# Schematic.net
KiCad netlist of a schematic drawn in Altium Designer
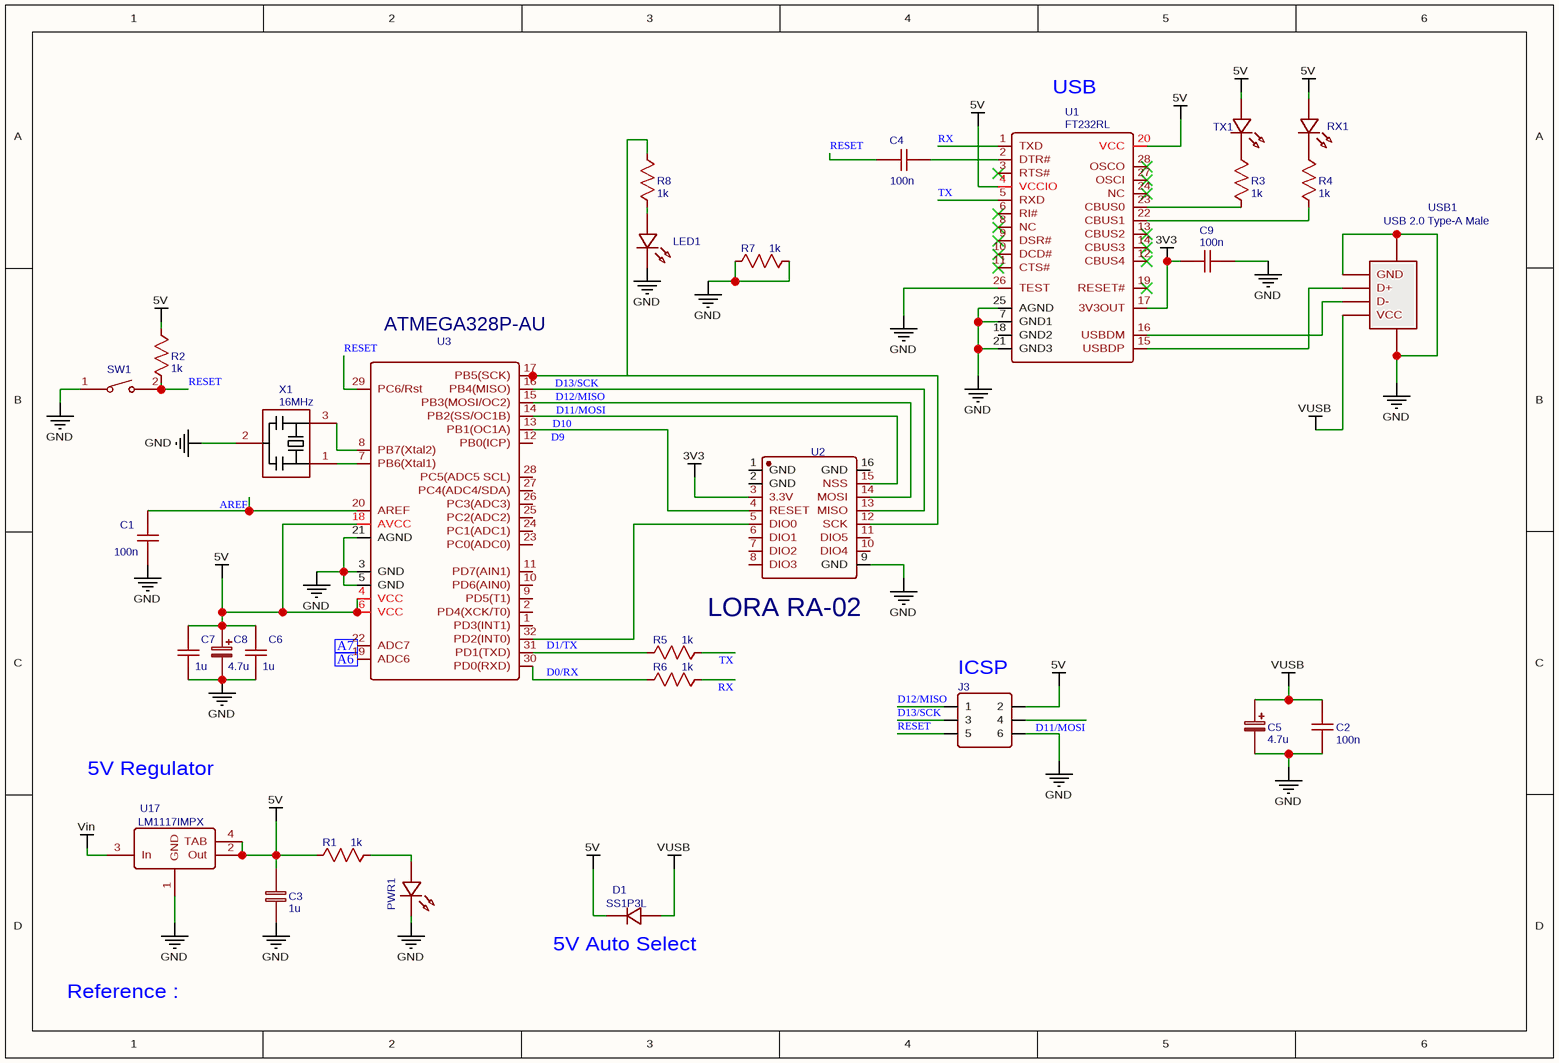
[diagram p0: Schematic.schdoc]

(export (version "E")
  (design (tool "Eeschema 10.0.6"))
  (components
    (comp (ref "C1")
      (value "100n")
      (fields (field (name "CONTRIBUTOR") "LCEDA_Lib"))
      (libsource (lib "altium-import") (part "root_3_100n_"))
    )
    (comp (ref "C2")
      (value "100n")
      (fields (field (name "CONTRIBUTOR") "LCEDA_Lib"))
      (libsource (lib "altium-import") (part "root_3_100n_"))
    )
    (comp (ref "C3")
      (value "1u")
      (fields (field (name "CONTRIBUTOR") "LCEDA_Lib"))
      (libsource (lib "altium-import") (part "root_1_1u_"))
    )
    (comp (ref "C4")
      (value "100n")
      (fields (field (name "CONTRIBUTOR") "LCEDA_Lib"))
      (libsource (lib "altium-import") (part "root_2_100n_"))
    )
    (comp (ref "C5")
      (value "4.7u")
      (fields (field (name "CONTRIBUTOR") "LCEDA_Lib"))
      (libsource (lib "altium-import") (part "root_3_4.7u_"))
    )
    (comp (ref "C6")
      (value "1u")
      (fields (field (name "CONTRIBUTOR") "LCEDA_Lib"))
      (libsource (lib "") (part "root_1_1u__1"))
    )
    (comp (ref "C7")
      (value "1u")
      (fields (field (name "CONTRIBUTOR") "LCEDA_Lib"))
      (libsource (lib "") (part "root_1_1u__1"))
    )
    (comp (ref "C8")
      (value "4.7u")
      (fields (field (name "CONTRIBUTOR") "LCEDA_Lib"))
      (libsource (lib "altium-import") (part "root_3_4.7u_"))
    )
    (comp (ref "C9")
      (value "100n")
      (fields (field (name "CONTRIBUTOR") "LCEDA_Lib"))
      (libsource (lib "altium-import") (part "root_0_100n_"))
    )
    (comp (ref "D1")
      (value "SS1P3L")
      (fields
        (field (name "MANUFACTURER") "Tak Cheong")
        (field (name "MANUFACTURER PART") "1N4148W")
        (field (name "CONTRIBUTOR") "LCEDA_Lib")
      )
      (libsource (lib "altium-import") (part "root_2_SS1P3L_"))
    )
    (comp (ref "J3")
      (value "HDR-M-2.54_2x3")
      (fields (field (name "CONTRIBUTOR") "LCEDA_Lib"))
      (libsource (lib "altium-import") (part "root_0_HDR-M-2.54_2x3_"))
    )
    (comp (ref "LED1")
      (value "LED-0603_B")
      (fields
        (field (name "MANUFACTURER") "EVERLIGHT(台湾亿光)")
        (field (name "MANUFACTURER PART") "19-217/BHC-ZL1M2RY/3T")
        (field (name "CONTRIBUTOR") "LCEDA_01")
      )
      (libsource (lib "altium-import") (part "root_3_LED-0603_B_"))
    )
    (comp (ref "PWR1")
      (value "LED-0603_G")
      (fields
        (field (name "MANUFACTURER") "EVERLIGHT(台湾亿光)")
        (field (name "MANUFACTURER PART") "19-217/GHC-YR1S2/3T")
        (field (name "CONTRIBUTOR") "LCEDA_Lib")
      )
      (libsource (lib "altium-import") (part "root_3_LED-0603_G_"))
    )
    (comp (ref "R1")
      (value "1k")
      (fields (field (name "CONTRIBUTOR") "LCEDA_Lib"))
      (libsource (lib "altium-import") (part "root_2_1k_"))
    )
    (comp (ref "R2")
      (value "1k")
      (fields (field (name "CONTRIBUTOR") "LCEDA_Lib"))
      (libsource (lib "altium-import") (part "root_1_1k_"))
    )
    (comp (ref "R3")
      (value "1k")
      (fields (field (name "CONTRIBUTOR") "LCEDA_Lib"))
      (libsource (lib "altium-import") (part "root_3_1k_"))
    )
    (comp (ref "R4")
      (value "1k")
      (fields (field (name "CONTRIBUTOR") "LCEDA_Lib"))
      (libsource (lib "altium-import") (part "root_3_1k_"))
    )
    (comp (ref "R5")
      (value "1k")
      (fields (field (name "CONTRIBUTOR") "LCEDA_Lib"))
      (libsource (lib "altium-import") (part "root_2_1k_"))
    )
    (comp (ref "R6")
      (value "1k")
      (fields (field (name "CONTRIBUTOR") "LCEDA_Lib"))
      (libsource (lib "altium-import") (part "root_2_1k_"))
    )
    (comp (ref "R7")
      (value "1k")
      (fields (field (name "CONTRIBUTOR") "LCEDA_Lib"))
      (libsource (lib "altium-import") (part "root_2_1k_"))
    )
    (comp (ref "R8")
      (value "1k")
      (fields (field (name "CONTRIBUTOR") "LCEDA_Lib"))
      (libsource (lib "altium-import") (part "root_3_1k_"))
    )
    (comp (ref "RX1")
      (value "LED-0603_R")
      (fields
        (field (name "MANUFACTURER") "EVERLIGHT(台湾亿光)")
        (field (name "MANUFACTURER PART") "19-217/R6C-AL1M2VY/3T")
        (field (name "CONTRIBUTOR") "LCEDA_01")
      )
      (libsource (lib "altium-import") (part "root_3_LED-0603_R_"))
    )
    (comp (ref "SW1")
      (value "TS-1088-AR02016")
      (fields (field (name "MANUFACTURER") "XUNPU") (field (name "CONTRIBUTOR") "LCSC"))
      (libsource (lib "altium-import") (part "root_0_TS-1088-AR02016_"))
    )
    (comp (ref "TX1")
      (value "LED-0603_G")
      (fields
        (field (name "MANUFACTURER") "EVERLIGHT(台湾亿光)")
        (field (name "MANUFACTURER PART") "19-217/GHC-YR1S2/3T")
        (field (name "CONTRIBUTOR") "LCEDA_Lib")
      )
      (libsource (lib "altium-import") (part "root_3_LED-0603_G_"))
    )
    (comp (ref "U1")
      (value "FT232RL")
      (fields (field (name "CONTRIBUTOR") "Alex_Tien"))
      (libsource (lib "altium-import") (part "root_0_FT232RL_"))
    )
    (comp (ref "U2")
      (value "LORA RA-02")
      (fields
        (field (name "MANUFACTURER PART") "LORA 专属定制版(公司内部定制,独一无二) RA-02")
        (field (name "CONTRIBUTOR") "LCSC")
      )
      (libsource (lib "altium-import") (part "root_0_LORA RA-02_"))
    )
    (comp (ref "U3")
      (value "ATMEGA328P-AU")
      (fields
        (field (name "MANUFACTURER") "Microchip Technology / Atmel")
        (field (name "CONTRIBUTOR") "Alex_Tien")
      )
      (libsource (lib "altium-import") (part "root_0_ATMEGA328P-AU_"))
    )
    (comp (ref "U17")
      (value "LM1117IMPX")
      (fields (field (name "MANUFACTURER") "AMS") (field (name "MANUFACTURER PART") "AMS1117-3.3"))
      (libsource (lib "altium-import") (part "root_0_LM1117IMPX_"))
    )
    (comp (ref "USB1")
      (value "USB 2.0 Type-A Male")
      (fields
        (field (name "MANUFACTURER") "ValuePro")
        (field (name "MANUFACTURER PART") "USB Male Plugin")
        (field (name "CONTRIBUTOR") "pyramidak")
      )
      (libsource (lib "altium-import") (part "root_2_USB 2.0 Type-A Male_"))
    )
    (comp (ref "X1")
      (value "16MHz")
      (fields
        (field (name "MANUFACTURER") "MuRata")
        (field (name "MANUFACTURER PART") "CSTCE16M0V53-R0")
        (field (name "CONTRIBUTOR") "Alex_Tien")
      )
      (libsource (lib "altium-import") (part "root_1_16MHz_"))
    )
  )
  (nets
    (net (code "1") (name "/A6") (class "Default")
      (node (ref "U3") (pin "19") (pinfunction "ADC6_19") (pintype "passive"))
    )
    (net (code "2") (name "/A7") (class "Default")
      (node (ref "U3") (pin "22") (pinfunction "ADC7_22") (pintype "passive"))
    )
    (net (code "3") (name "/AREF") (class "Default")
      (node (ref "C1") (pin "1") (pinfunction "1_1") (pintype "passive"))
      (node (ref "U3") (pin "20") (pinfunction "AREF_20") (pintype "passive"))
    )
    (net (code "4") (name "/D0{slash}RX") (class "Default")
      (node (ref "R6") (pin "2") (pinfunction "2_2") (pintype "passive"))
      (node (ref "U3") (pin "30") (pinfunction "PD0(RXD)_30") (pintype "passive"))
    )
    (net (code "5") (name "/D1{slash}TX") (class "Default")
      (node (ref "R5") (pin "2") (pinfunction "2_2") (pintype "passive"))
      (node (ref "U3") (pin "31") (pinfunction "PD1(TXD)_31") (pintype "passive"))
    )
    (net (code "6") (name "/D9") (class "Default")
      (node (ref "U2") (pin "4") (pinfunction "RESET_4") (pintype "passive"))
      (node (ref "U3") (pin "13") (pinfunction "PB1(OC1A)_13") (pintype "passive"))
    )
    (net (code "7") (name "/D10") (class "Default")
      (node (ref "U2") (pin "15") (pinfunction "NSS_15") (pintype "passive"))
      (node (ref "U3") (pin "14") (pinfunction "PB2(SS/OC1B)_14") (pintype "passive"))
    )
    (net (code "8") (name "/D11{slash}MOSI") (class "Default")
      (node (ref "J3") (pin "4") (pinfunction "4_4") (pintype "passive"))
      (node (ref "U2") (pin "14") (pinfunction "MOSI_14") (pintype "passive"))
      (node (ref "U3") (pin "15") (pinfunction "PB3(MOSI/OC2)_15") (pintype "passive"))
    )
    (net (code "9") (name "/D12{slash}MISO") (class "Default")
      (node (ref "J3") (pin "1") (pinfunction "1_1") (pintype "passive"))
      (node (ref "U2") (pin "13") (pinfunction "MISO_13") (pintype "passive"))
      (node (ref "U3") (pin "16") (pinfunction "PB4(MISO)_16") (pintype "passive"))
    )
    (net (code "10") (name "/D13{slash}SCK") (class "Default")
      (node (ref "J3") (pin "3") (pinfunction "3_3") (pintype "passive"))
      (node (ref "R8") (pin "1") (pinfunction "1_1") (pintype "passive"))
      (node (ref "U2") (pin "12") (pinfunction "SCK_12") (pintype "passive"))
      (node (ref "U3") (pin "17") (pinfunction "PB5(SCK)_17") (pintype "passive"))
    )
    (net (code "11") (name "/RESET") (class "Default")
      (node (ref "C4") (pin "2") (pinfunction "2_2") (pintype "passive"))
      (node (ref "J3") (pin "5") (pinfunction "5_5") (pintype "passive"))
      (node (ref "R2") (pin "1") (pinfunction "1_1") (pintype "passive"))
      (node (ref "SW1") (pin "2") (pinfunction "2_2") (pintype "passive"))
      (node (ref "U3") (pin "29") (pinfunction "PC6/Rst_29") (pintype "passive"))
    )
    (net (code "12") (name "/RX") (class "Default")
      (node (ref "R6") (pin "1") (pinfunction "1_1") (pintype "passive"))
      (node (ref "U1") (pin "1") (pinfunction "TXD_1") (pintype "passive"))
    )
    (net (code "13") (name "/TX") (class "Default")
      (node (ref "R5") (pin "1") (pinfunction "1_1") (pintype "passive"))
      (node (ref "U1") (pin "5") (pinfunction "RXD_5") (pintype "passive"))
    )
    (net (code "14") (name "3V3") (class "Default")
      (node (ref "C9") (pin "1") (pinfunction "1_1") (pintype "passive"))
      (node (ref "U1") (pin "17") (pinfunction "3V3OUT_17") (pintype "passive"))
      (node (ref "U2") (pin "3") (pinfunction "3.3V_3") (pintype "passive"))
    )
    (net (code "15") (name "5V") (class "Default")
      (node (ref "C3") (pin "2") (pinfunction "2_2") (pintype "passive"))
      (node (ref "C6") (pin "2") (pinfunction "2_2") (pintype "passive"))
      (node (ref "C7") (pin "2") (pinfunction "2_2") (pintype "passive"))
      (node (ref "C8") (pin "1") (pinfunction "1_1") (pintype "passive"))
      (node (ref "D1") (pin "1") (pinfunction "1_1") (pintype "passive"))
      (node (ref "J3") (pin "2") (pinfunction "2_2") (pintype "passive"))
      (node (ref "R1") (pin "2") (pinfunction "2_2") (pintype "passive"))
      (node (ref "R2") (pin "2") (pinfunction "2_2") (pintype "passive"))
      (node (ref "RX1") (pin "1") (pinfunction "1_1") (pintype "passive"))
      (node (ref "TX1") (pin "1") (pinfunction "1_1") (pintype "passive"))
      (node (ref "U1") (pin "20") (pinfunction "VCC_20") (pintype "passive"))
      (node (ref "U1") (pin "4") (pinfunction "VCCIO_4") (pintype "passive"))
      (node (ref "U17") (pin "2") (pinfunction "Out_2") (pintype "passive"))
      (node (ref "U17") (pin "4") (pinfunction "TAB_4") (pintype "passive"))
      (node (ref "U3") (pin "18") (pinfunction "AVCC_18") (pintype "passive"))
      (node (ref "U3") (pin "4") (pinfunction "VCC_4") (pintype "passive"))
      (node (ref "U3") (pin "6") (pinfunction "VCC_6") (pintype "passive"))
    )
    (net (code "16") (name "GND") (class "Default")
      (node (ref "C1") (pin "2") (pinfunction "2_2") (pintype "passive"))
      (node (ref "C2") (pin "2") (pinfunction "2_2") (pintype "passive"))
      (node (ref "C3") (pin "1") (pinfunction "1_1") (pintype "passive"))
      (node (ref "C5") (pin "2") (pinfunction "2_2") (pintype "passive"))
      (node (ref "C6") (pin "1") (pinfunction "1_1") (pintype "passive"))
      (node (ref "C7") (pin "1") (pinfunction "1_1") (pintype "passive"))
      (node (ref "C8") (pin "2") (pinfunction "2_2") (pintype "passive"))
      (node (ref "C9") (pin "2") (pinfunction "2_2") (pintype "passive"))
      (node (ref "J3") (pin "6") (pinfunction "6_6") (pintype "passive"))
      (node (ref "LED1") (pin "2") (pinfunction "2_2") (pintype "passive"))
      (node (ref "PWR1") (pin "2") (pinfunction "2_2") (pintype "passive"))
      (node (ref "R7") (pin "1") (pinfunction "1_1") (pintype "passive"))
      (node (ref "R7") (pin "2") (pinfunction "2_2") (pintype "passive"))
      (node (ref "SW1") (pin "1") (pinfunction "1_1") (pintype "passive"))
      (node (ref "U1") (pin "21") (pinfunction "GND3_21") (pintype "passive"))
      (node (ref "U1") (pin "25") (pinfunction "AGND_25") (pintype "passive"))
      (node (ref "U1") (pin "26") (pinfunction "TEST_26") (pintype "passive"))
      (node (ref "U1") (pin "7") (pinfunction "GND1_7") (pintype "passive"))
      (node (ref "U17") (pin "1") (pinfunction "GND_1") (pintype "passive"))
      (node (ref "U2") (pin "9") (pinfunction "GND_9") (pintype "passive"))
      (node (ref "U3") (pin "21") (pinfunction "AGND_21") (pintype "passive"))
      (node (ref "U3") (pin "3") (pinfunction "GND_3") (pintype "passive"))
      (node (ref "U3") (pin "5") (pinfunction "GND_5") (pintype "passive"))
      (node (ref "USB1") (pin "0") (pinfunction "0_0") (pintype "passive"))
      (node (ref "USB1") (pin "4") (pinfunction "GND_4") (pintype "passive"))
      (node (ref "USB1") (pin "6") (pinfunction "0_6") (pintype "passive"))
      (node (ref "X1") (pin "2") (pinfunction "2_2") (pintype "passive"))
    )
    (net (code "17") (name "Net-(LED1-Pad1)") (class "Default")
      (node (ref "LED1") (pin "1") (pinfunction "1_1") (pintype "passive"))
      (node (ref "R8") (pin "2") (pinfunction "2_2") (pintype "passive"))
    )
    (net (code "18") (name "Net-(PWR1-Pad1)") (class "Default")
      (node (ref "PWR1") (pin "1") (pinfunction "1_1") (pintype "passive"))
      (node (ref "R1") (pin "1") (pinfunction "1_1") (pintype "passive"))
    )
    (net (code "19") (name "Net-(R3-Pad1)") (class "Default")
      (node (ref "R3") (pin "1") (pinfunction "1_1") (pintype "passive"))
      (node (ref "TX1") (pin "2") (pinfunction "2_2") (pintype "passive"))
    )
    (net (code "20") (name "Net-(R4-Pad1)") (class "Default")
      (node (ref "R4") (pin "1") (pinfunction "1_1") (pintype "passive"))
      (node (ref "RX1") (pin "2") (pinfunction "2_2") (pintype "passive"))
    )
    (net (code "21") (name "Net-(U1-CBUS0)") (class "Default")
      (node (ref "R3") (pin "2") (pinfunction "2_2") (pintype "passive"))
      (node (ref "U1") (pin "23") (pinfunction "CBUS0_23") (pintype "passive"))
    )
    (net (code "22") (name "Net-(U1-CBUS1)") (class "Default")
      (node (ref "R4") (pin "2") (pinfunction "2_2") (pintype "passive"))
      (node (ref "U1") (pin "22") (pinfunction "CBUS1_22") (pintype "passive"))
    )
    (net (code "23") (name "Net-(U1-DTR#)") (class "Default")
      (node (ref "C4") (pin "1") (pinfunction "1_1") (pintype "passive"))
      (node (ref "U1") (pin "2") (pinfunction "DTR#_2") (pintype "passive"))
    )
    (net (code "24") (name "Net-(U1-USBDM)") (class "Default")
      (node (ref "U1") (pin "16") (pinfunction "USBDM_16") (pintype "passive"))
      (node (ref "USB1") (pin "2") (pinfunction "D-_2") (pintype "passive"))
    )
    (net (code "25") (name "Net-(U1-USBDP)") (class "Default")
      (node (ref "U1") (pin "15") (pinfunction "USBDP_15") (pintype "passive"))
      (node (ref "USB1") (pin "3") (pinfunction "D+_3") (pintype "passive"))
    )
    (net (code "26") (name "Net-(U2-DIO0)") (class "Default")
      (node (ref "U2") (pin "5") (pinfunction "DIO0_5") (pintype "passive"))
      (node (ref "U3") (pin "32") (pinfunction "PD2(INT0)_32") (pintype "passive"))
    )
    (net (code "27") (name "Net-(U3-PB6(Xtal1))") (class "Default")
      (node (ref "U3") (pin "7") (pinfunction "PB6(Xtal1)_7") (pintype "passive"))
      (node (ref "X1") (pin "1") (pinfunction "1_1") (pintype "passive"))
    )
    (net (code "28") (name "Net-(U3-PB7(Xtal2))") (class "Default")
      (node (ref "U3") (pin "8") (pinfunction "PB7(Xtal2)_8") (pintype "passive"))
      (node (ref "X1") (pin "3") (pinfunction "3_3") (pintype "passive"))
    )
    (net (code "29") (name "VUSB") (class "Default")
      (node (ref "C2") (pin "1") (pinfunction "1_1") (pintype "passive"))
      (node (ref "C5") (pin "1") (pinfunction "1_1") (pintype "passive"))
      (node (ref "D1") (pin "2") (pinfunction "2_2") (pintype "passive"))
      (node (ref "USB1") (pin "1") (pinfunction "VCC_1") (pintype "passive"))
    )
    (net (code "30") (name "Vin") (class "Default")
      (node (ref "U17") (pin "3") (pinfunction "In_3") (pintype "passive"))
    )
    (net (code "31") (name "unconnected-(U1-CBUS2-Pad13)") (class "Default")
      (node (ref "U1") (pin "13") (pinfunction "CBUS2_13") (pintype "passive+no_connect"))
    )
    (net (code "32") (name "unconnected-(U1-CBUS3-Pad14)") (class "Default")
      (node (ref "U1") (pin "14") (pinfunction "CBUS3_14") (pintype "passive+no_connect"))
    )
    (net (code "33") (name "unconnected-(U1-CBUS4-Pad12)") (class "Default")
      (node (ref "U1") (pin "12") (pinfunction "CBUS4_12") (pintype "passive+no_connect"))
    )
    (net (code "34") (name "unconnected-(U1-CTS#-Pad11)") (class "Default")
      (node (ref "U1") (pin "11") (pinfunction "CTS#_11") (pintype "passive+no_connect"))
    )
    (net (code "35") (name "unconnected-(U1-DCD#-Pad10)") (class "Default")
      (node (ref "U1") (pin "10") (pinfunction "DCD#_10") (pintype "passive+no_connect"))
    )
    (net (code "36") (name "unconnected-(U1-DSR#-Pad9)") (class "Default")
      (node (ref "U1") (pin "9") (pinfunction "DSR#_9") (pintype "passive+no_connect"))
    )
    (net (code "37") (name "unconnected-(U1-GND2-Pad18)") (class "Default")
      (node (ref "U1") (pin "18") (pinfunction "GND2_18") (pintype "passive"))
    )
    (net (code "38") (name "unconnected-(U1-NC-Pad8)") (class "Default")
      (node (ref "U1") (pin "8") (pinfunction "NC_8") (pintype "passive+no_connect"))
    )
    (net (code "39") (name "unconnected-(U1-NC-Pad24)") (class "Default")
      (node (ref "U1") (pin "24") (pinfunction "NC_24") (pintype "passive+no_connect"))
    )
    (net (code "40") (name "unconnected-(U1-OSCI-Pad27)") (class "Default")
      (node (ref "U1") (pin "27") (pinfunction "OSCI_27") (pintype "passive+no_connect"))
    )
    (net (code "41") (name "unconnected-(U1-OSCO-Pad28)") (class "Default")
      (node (ref "U1") (pin "28") (pinfunction "OSCO_28") (pintype "passive+no_connect"))
    )
    (net (code "42") (name "unconnected-(U1-RESET#-Pad19)") (class "Default")
      (node (ref "U1") (pin "19") (pinfunction "RESET#_19") (pintype "passive+no_connect"))
    )
    (net (code "43") (name "unconnected-(U1-RI#-Pad6)") (class "Default")
      (node (ref "U1") (pin "6") (pinfunction "RI#_6") (pintype "passive+no_connect"))
    )
    (net (code "44") (name "unconnected-(U1-RTS#-Pad3)") (class "Default")
      (node (ref "U1") (pin "3") (pinfunction "RTS#_3") (pintype "passive+no_connect"))
    )
    (net (code "45") (name "unconnected-(U2-DIO1-Pad6)") (class "Default")
      (node (ref "U2") (pin "6") (pinfunction "DIO1_6") (pintype "passive"))
    )
    (net (code "46") (name "unconnected-(U2-DIO2-Pad7)") (class "Default")
      (node (ref "U2") (pin "7") (pinfunction "DIO2_7") (pintype "passive"))
    )
    (net (code "47") (name "unconnected-(U2-DIO3-Pad8)") (class "Default")
      (node (ref "U2") (pin "8") (pinfunction "DIO3_8") (pintype "passive"))
    )
    (net (code "48") (name "unconnected-(U2-DIO4-Pad10)") (class "Default")
      (node (ref "U2") (pin "10") (pinfunction "DIO4_10") (pintype "passive"))
    )
    (net (code "49") (name "unconnected-(U2-DIO5-Pad11)") (class "Default")
      (node (ref "U2") (pin "11") (pinfunction "DIO5_11") (pintype "passive"))
    )
    (net (code "50") (name "unconnected-(U2-GND-Pad1)") (class "Default")
      (node (ref "U2") (pin "1") (pinfunction "GND_1") (pintype "passive"))
    )
    (net (code "51") (name "unconnected-(U2-GND-Pad2)") (class "Default")
      (node (ref "U2") (pin "2") (pinfunction "GND_2") (pintype "passive"))
    )
    (net (code "52") (name "unconnected-(U2-GND-Pad16)") (class "Default")
      (node (ref "U2") (pin "16") (pinfunction "GND_16") (pintype "passive"))
    )
    (net (code "53") (name "unconnected-(U3-PB0(ICP)-Pad12)") (class "Default")
      (node (ref "U3") (pin "12") (pinfunction "PB0(ICP)_12") (pintype "passive"))
    )
    (net (code "54") (name "unconnected-(U3-PC0(ADC0)-Pad23)") (class "Default")
      (node (ref "U3") (pin "23") (pinfunction "PC0(ADC0)_23") (pintype "passive"))
    )
    (net (code "55") (name "unconnected-(U3-PC1(ADC1)-Pad24)") (class "Default")
      (node (ref "U3") (pin "24") (pinfunction "PC1(ADC1)_24") (pintype "passive"))
    )
    (net (code "56") (name "unconnected-(U3-PC2(ADC2)-Pad25)") (class "Default")
      (node (ref "U3") (pin "25") (pinfunction "PC2(ADC2)_25") (pintype "passive"))
    )
    (net (code "57") (name "unconnected-(U3-PC3(ADC3)-Pad26)") (class "Default")
      (node (ref "U3") (pin "26") (pinfunction "PC3(ADC3)_26") (pintype "passive"))
    )
    (net (code "58") (name "unconnected-(U3-PC4(ADC4{slash}SDA)-Pad27)") (class "Default")
      (node (ref "U3") (pin "27") (pinfunction "PC4(ADC4/SDA)_27") (pintype "passive"))
    )
    (net (code "59") (name "unconnected-(U3-PC5(ADC5_SCL)-Pad28)") (class "Default")
      (node (ref "U3") (pin "28") (pinfunction "PC5(ADC5_SCL)_28") (pintype "passive"))
    )
    (net (code "60") (name "unconnected-(U3-PD3(INT1)-Pad1)") (class "Default")
      (node (ref "U3") (pin "1") (pinfunction "PD3(INT1)_1") (pintype "passive"))
    )
    (net (code "61") (name "unconnected-(U3-PD4(XCK{slash}T0)-Pad2)") (class "Default")
      (node (ref "U3") (pin "2") (pinfunction "PD4(XCK/T0)_2") (pintype "passive"))
    )
    (net (code "62") (name "unconnected-(U3-PD5(T1)-Pad9)") (class "Default")
      (node (ref "U3") (pin "9") (pinfunction "PD5(T1)_9") (pintype "passive"))
    )
    (net (code "63") (name "unconnected-(U3-PD6(AIN0)-Pad10)") (class "Default")
      (node (ref "U3") (pin "10") (pinfunction "PD6(AIN0)_10") (pintype "passive"))
    )
    (net (code "64") (name "unconnected-(U3-PD7(AIN1)-Pad11)") (class "Default")
      (node (ref "U3") (pin "11") (pinfunction "PD7(AIN1)_11") (pintype "passive"))
    )
  )
)
